# accelerometer_soft_spi.net
KiCad netlist of a schematic drawn in EAGLE
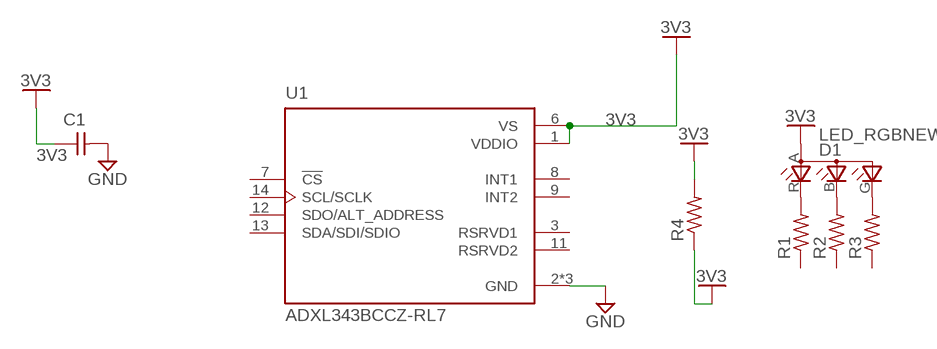
[diagram p0: schematic, sheet 1]

(export (version "E")
  (design (tool "Eeschema 10.0.6"))
  (components
    (comp (ref "C1")
      (value "CAP_UNPOLARIZED")
      (footprint "eagle-import:C1206")
      (libsource (lib "eagle-import") (part "CAP_UNPOLARIZED"))
    )
    (comp (ref "D1")
      (value "LED_RGBNEW")
      (footprint "eagle-import:P-LCC-4")
      (libsource (lib "eagle-import") (part "LED_RGBNEW"))
    )
    (comp (ref "R1")
      (value "R1206")
      (footprint "eagle-import:R1206")
      (libsource (lib "eagle-import") (part "R1206"))
    )
    (comp (ref "R2")
      (value "R1206")
      (footprint "eagle-import:R1206")
      (libsource (lib "eagle-import") (part "R1206"))
    )
    (comp (ref "R3")
      (value "R1206")
      (footprint "eagle-import:R1206")
      (libsource (lib "eagle-import") (part "R1206"))
    )
    (comp (ref "R4")
      (value "R1206")
      (footprint "eagle-import:R1206")
      (libsource (lib "eagle-import") (part "R1206"))
    )
    (comp (ref "U1")
      (value "ADXL343BCCZ-RL7")
      (footprint "eagle-import:PQFN80P300X500X100-14N")
      (fields (field (name "MF") "Analog Devices"))
      (libsource (lib "eagle-import") (part "ADXL343BCCZ-RL7"))
    )
  )
  (nets
    (net (code "1") (name "3V3") (class "Default")
      (node (ref "C1") (pin "1") (pinfunction "1_1") (pintype "passive"))
      (node (ref "D1") (pin "A") (pinfunction "A2_A") (pintype "passive"))
      (node (ref "R4") (pin "1") (pinfunction "1_1") (pintype "passive"))
      (node (ref "R4") (pin "2") (pinfunction "2_2") (pintype "passive"))
      (node (ref "U1") (pin "1") (pinfunction "VDDIO_1") (pintype "power_in"))
      (node (ref "U1") (pin "6") (pinfunction "VS_6") (pintype "power_in"))
    )
    (net (code "2") (name "GND") (class "Default")
      (node (ref "C1") (pin "2") (pinfunction "2_2") (pintype "passive"))
      (node (ref "U1") (pin "2") (pinfunction "GND_2") (pintype "power_in"))
      (node (ref "U1") (pin "4") (pinfunction "GND_4") (pintype "power_in"))
      (node (ref "U1") (pin "5") (pinfunction "GND_5") (pintype "power_in"))
    )
    (net (code "3") (name "Net-(D1-CBLUE)") (class "Default")
      (node (ref "D1") (pin "B") (pinfunction "CBLUE_B") (pintype "passive"))
      (node (ref "R2") (pin "2") (pinfunction "2_2") (pintype "passive"))
    )
    (net (code "4") (name "Net-(D1-CGREEN)") (class "Default")
      (node (ref "D1") (pin "G") (pinfunction "CGREEN_G") (pintype "passive"))
      (node (ref "R3") (pin "2") (pinfunction "2_2") (pintype "passive"))
    )
    (net (code "5") (name "Net-(D1-CRED)") (class "Default")
      (node (ref "D1") (pin "R") (pinfunction "CRED_R") (pintype "passive"))
      (node (ref "R1") (pin "2") (pinfunction "2_2") (pintype "passive"))
    )
    (net (code "6") (name "unconnected-(R1-Pad1)") (class "Default")
      (node (ref "R1") (pin "1") (pinfunction "1_1") (pintype "passive"))
    )
    (net (code "7") (name "unconnected-(R2-Pad1)") (class "Default")
      (node (ref "R2") (pin "1") (pinfunction "1_1") (pintype "passive"))
    )
    (net (code "8") (name "unconnected-(R3-Pad1)") (class "Default")
      (node (ref "R3") (pin "1") (pinfunction "1_1") (pintype "passive"))
    )
    (net (code "9") (name "unconnected-(U1-INT1-Pad8)") (class "Default")
      (node (ref "U1") (pin "8") (pinfunction "INT1_8") (pintype "output"))
    )
    (net (code "10") (name "unconnected-(U1-INT2-Pad9)") (class "Default")
      (node (ref "U1") (pin "9") (pinfunction "INT2_9") (pintype "output"))
    )
    (net (code "11") (name "unconnected-(U1-RSRVD1-Pad3)") (class "Default")
      (node (ref "U1") (pin "3") (pinfunction "RSRVD1_3") (pintype "passive"))
    )
    (net (code "12") (name "unconnected-(U1-RSRVD2-Pad11)") (class "Default")
      (node (ref "U1") (pin "11") (pinfunction "RSRVD2_11") (pintype "passive"))
    )
    (net (code "13") (name "unconnected-(U1-SCL{slash}SCLK-Pad14)") (class "Default")
      (node (ref "U1") (pin "14") (pinfunction "SCL/SCLK_14") (pintype "input"))
    )
    (net (code "14") (name "unconnected-(U1-SDA{slash}SDI{slash}SDIO-Pad13)") (class "Default")
      (node (ref "U1") (pin "13") (pinfunction "SDA/SDI/SDIO_13") (pintype "bidirectional"))
    )
    (net (code "15") (name "unconnected-(U1-SDO{slash}ALT_ADDRESS-Pad12)") (class "Default")
      (node (ref "U1") (pin "12") (pinfunction "SDO/ALT_ADDRESS_12") (pintype "bidirectional"))
    )
    (net (code "16") (name "unconnected-(U1-~{CS}-Pad7)") (class "Default")
      (node (ref "U1") (pin "7") (pinfunction "~{CS}_7") (pintype "input"))
    )
  )
)
